# Sheet1.net
KiCad netlist of a schematic drawn in Altium Designer
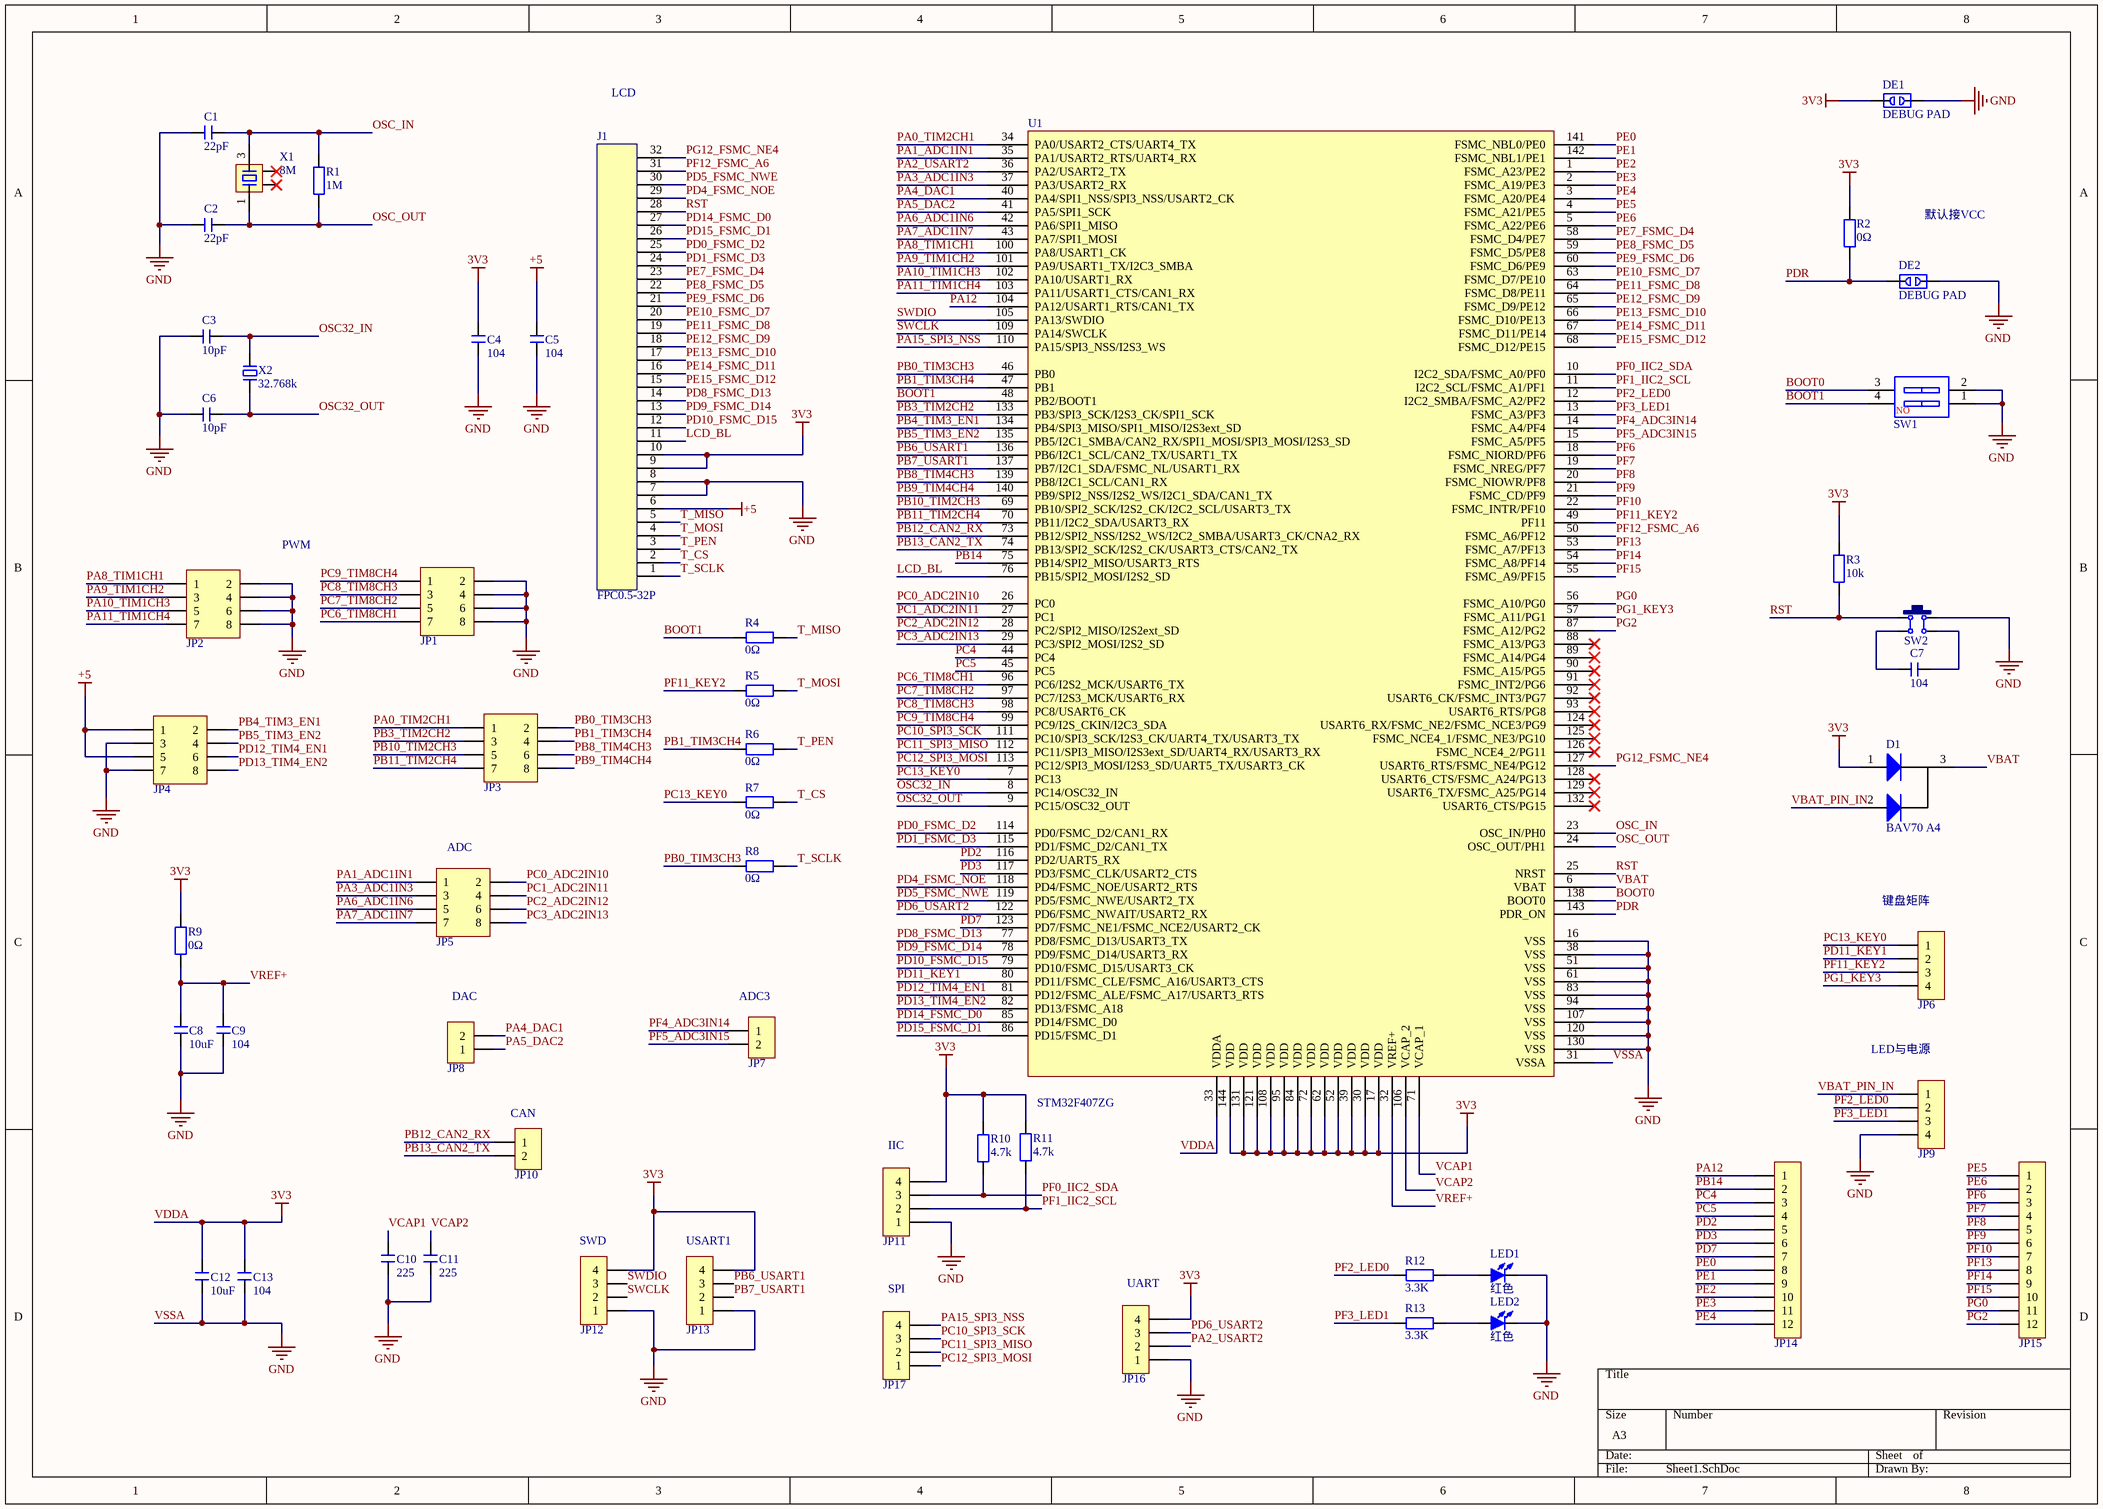
[diagram p0: Sheet1.SchDoc]

(export (version "E")
  (design (tool "Eeschema 10.0.6"))
  (components
    (comp (ref "C1")
      (value "22pF")
      (footprint "C 0603_L")
      (description "无极性贴片电容")
      (fields (field (name "版权归属") "源创客"))
      (libsource (lib "3.1   - 电阻-电容-电感") (part "C"))
    )
    (comp (ref "C2")
      (value "22pF")
      (footprint "C 0603_L")
      (description "无极性贴片电容")
      (fields (field (name "版权归属") "源创客"))
      (libsource (lib "3.1   - 电阻-电容-电感") (part "C"))
    )
    (comp (ref "C3")
      (value "10pF")
      (footprint "C 0603_L")
      (description "无极性贴片电容")
      (fields (field (name "版权归属") "源创客"))
      (libsource (lib "3.1   - 电阻-电容-电感") (part "C"))
    )
    (comp (ref "C4")
      (value "104")
      (footprint "C 0603_L")
      (description "无极性贴片电容")
      (fields (field (name "版权归属") "源创客"))
      (libsource (lib "3.1   - 电阻-电容-电感") (part "C"))
    )
    (comp (ref "C5")
      (value "104")
      (footprint "C 0603_L")
      (description "无极性贴片电容")
      (fields (field (name "版权归属") "源创客"))
      (libsource (lib "3.1   - 电阻-电容-电感") (part "C"))
    )
    (comp (ref "C6")
      (value "10pF")
      (footprint "C 0603_L")
      (description "无极性贴片电容")
      (fields (field (name "版权归属") "源创客"))
      (libsource (lib "3.1   - 电阻-电容-电感") (part "C"))
    )
    (comp (ref "C7")
      (value "104")
      (footprint "C 0603_L")
      (description "无极性贴片电容")
      (fields (field (name "版权归属") "源创客"))
      (libsource (lib "3.1   - 电阻-电容-电感") (part "C"))
    )
    (comp (ref "C8")
      (value "10uF")
      (footprint "C 0603_L")
      (description "无极性贴片电容")
      (fields (field (name "版权归属") "源创客"))
      (libsource (lib "3.1   - 电阻-电容-电感") (part "C"))
    )
    (comp (ref "C9")
      (value "104")
      (footprint "C 0603_L")
      (description "无极性贴片电容")
      (fields (field (name "版权归属") "源创客"))
      (libsource (lib "3.1   - 电阻-电容-电感") (part "C"))
    )
    (comp (ref "C10")
      (value "225")
      (footprint "C 0603_L")
      (description "无极性贴片电容")
      (fields (field (name "版权归属") "源创客"))
      (libsource (lib "3.1   - 电阻-电容-电感") (part "C"))
    )
    (comp (ref "C11")
      (value "225")
      (footprint "C 0603_L")
      (description "无极性贴片电容")
      (fields (field (name "版权归属") "源创客"))
      (libsource (lib "3.1   - 电阻-电容-电感") (part "C"))
    )
    (comp (ref "C12")
      (value "10uF")
      (footprint "C 0603_L")
      (description "无极性贴片电容")
      (fields (field (name "版权归属") "源创客"))
      (libsource (lib "3.1   - 电阻-电容-电感") (part "C"))
    )
    (comp (ref "C13")
      (value "104")
      (footprint "C 0603_L")
      (description "无极性贴片电容")
      (fields (field (name "版权归属") "源创客"))
      (libsource (lib "3.1   - 电阻-电容-电感") (part "C"))
    )
    (comp (ref "D1")
      (value "BAV70 A4")
      (footprint "SOT-23(SOT-23-3)")
      (description "开关二极管")
      (libsource (lib "Miscellaneous Devices LC") (part "SOT-23 BAV70 A4"))
    )
    (comp (ref "DE1")
      (value "DEBUG PAD")
      (footprint "DEBUG_A")
      (description "调试断点焊盘")
      (fields (field (name "版权归属") "源创客"))
      (libsource (lib "15.1 - 未分类器件") (part "DEBUG"))
    )
    (comp (ref "DE2")
      (value "DEBUG PAD")
      (footprint "DEBUG_A")
      (description "调试断点焊盘")
      (fields (field (name "版权归属") "源创客"))
      (libsource (lib "15.1 - 未分类器件") (part "DEBUG"))
    )
    (comp (ref "J1")
      (value "FPC0.5-32P")
      (footprint "FPC0.5-32P")
      (description "贴片")
      (libsource (lib "FPC") (part "FPC0.5-32P"))
    )
    (comp (ref "JP1")
      (value "Header 4X2")
      (footprint "HDR2.54-LI-2x4P")
      (description "4*2P接插件")
      (fields (field (name "版权归属") "源创客"))
      (libsource (lib "4.5   - 接插件-脚距2.54") (part "Header 4X2"))
    )
    (comp (ref "JP2")
      (value "Header 4X2")
      (footprint "HDR2.54-LI-2x4P")
      (description "4*2P接插件")
      (fields (field (name "版权归属") "源创客"))
      (libsource (lib "4.5   - 接插件-脚距2.54") (part "Header 4X2"))
    )
    (comp (ref "JP3")
      (value "Header 4X2")
      (footprint "HDR2.54-LI-2x4P")
      (description "4*2P接插件")
      (fields (field (name "版权归属") "源创客"))
      (libsource (lib "4.5   - 接插件-脚距2.54") (part "Header 4X2"))
    )
    (comp (ref "JP4")
      (value "Header 4X2")
      (footprint "HDR2.54-LI-2x4P")
      (description "4*2P接插件")
      (fields (field (name "版权归属") "源创客"))
      (libsource (lib "4.5   - 接插件-脚距2.54") (part "Header 4X2"))
    )
    (comp (ref "JP5")
      (value "Header 4X2")
      (footprint "HDR2.54-LI-2x4P")
      (description "4*2P接插件")
      (fields (field (name "版权归属") "源创客"))
      (libsource (lib "4.5   - 接插件-脚距2.54") (part "Header 4X2"))
    )
    (comp (ref "JP6")
      (value "HDR-1X4")
      (footprint "HDR2.54-LI-4P")
      (description "4P接插件")
      (fields (field (name "版权归属") "源创客"))
      (libsource (lib "") (part "Header 4_1"))
    )
    (comp (ref "JP7")
      (value "HDR-1X2")
      (footprint "KF128-3.81-2P")
      (description "2P接插件")
      (fields (field (name "版权归属") "源创客"))
      (libsource (lib "4.7   - 接插件-脚距3.81") (part "Header 2"))
    )
    (comp (ref "JP8")
      (value "HDR-1X2")
      (footprint "HDR2.54-LI-2P")
      (description "2P接插件")
      (fields (field (name "版权归属") "源创客"))
      (libsource (lib "4.5   - 接插件-脚距2.54") (part "Header 2"))
    )
    (comp (ref "JP9")
      (value "HDR-1X4")
      (footprint "HDR2.54-LI-4P")
      (description "4P接插件")
      (fields (field (name "版权归属") "源创客"))
      (libsource (lib "") (part "Header 4_1"))
    )
    (comp (ref "JP10")
      (value "HDR-1X2")
      (footprint "KF350-2P")
      (description "2P接插件")
      (fields (field (name "版权归属") "源创客"))
      (libsource (lib "4.6   - 接插件-脚距3.5") (part "Header 2"))
    )
    (comp (ref "JP11")
      (value "HDR-1X4")
      (footprint "HDR2.54-LI-4P")
      (description "4P接插件")
      (fields (field (name "版权归属") "源创客"))
      (libsource (lib "4.5   - 接插件-脚距2.54") (part "Header 4"))
    )
    (comp (ref "JP12")
      (value "HDR-1X4")
      (footprint "HDR2.54-LI-4P")
      (description "4P接插件")
      (fields (field (name "版权归属") "源创客"))
      (libsource (lib "4.5   - 接插件-脚距2.54") (part "Header 4"))
    )
    (comp (ref "JP13")
      (value "HDR-1X4")
      (footprint "HDR2.54-LI-4P")
      (description "4P接插件")
      (fields (field (name "版权归属") "源创客"))
      (libsource (lib "4.5   - 接插件-脚距2.54") (part "Header 4"))
    )
    (comp (ref "JP14")
      (value "HDR-1X12")
      (footprint "HDR2.54-LI-12P")
      (description "12P接插件")
      (fields (field (name "版权归属") "源创客"))
      (libsource (lib "4.5   - 接插件-脚距2.54") (part "Header 12"))
    )
    (comp (ref "JP15")
      (value "HDR-1X12")
      (footprint "HDR2.54-LI-12P")
      (description "12P接插件")
      (fields (field (name "版权归属") "源创客"))
      (libsource (lib "4.5   - 接插件-脚距2.54") (part "Header 12"))
    )
    (comp (ref "JP16")
      (value "HDR-1X4")
      (footprint "HDR2.54-LI-4P")
      (description "4P接插件")
      (fields (field (name "版权归属") "源创客"))
      (libsource (lib "4.5   - 接插件-脚距2.54") (part "Header 4"))
    )
    (comp (ref "JP17")
      (value "HDR-1X4")
      (footprint "HDR2.54-LI-4P")
      (description "4P接插件")
      (fields (field (name "版权归属") "源创客"))
      (libsource (lib "4.5   - 接插件-脚距2.54") (part "Header 4"))
    )
    (comp (ref "LED1")
      (value "红色")
      (footprint "LED 0603R")
      (description "贴片LED")
      (fields (field (name "版权归属") "源创客"))
      (libsource (lib "9.1   - LED") (part "LED-SMD"))
    )
    (comp (ref "LED2")
      (value "红色")
      (footprint "LED 0603B")
      (description "贴片LED")
      (fields (field (name "版权归属") "源创客"))
      (libsource (lib "9.1   - LED") (part "LED-SMD"))
    )
    (comp (ref "R1")
      (value "1M")
      (footprint "R 0603_L")
      (description "贴片电阻")
      (fields (field (name "版权归属") "源创客"))
      (libsource (lib "3.1   - 电阻-电容-电感") (part "R"))
    )
    (comp (ref "R2")
      (value "0Ω")
      (footprint "R 0603_L")
      (description "贴片电阻")
      (fields (field (name "版权归属") "源创客"))
      (libsource (lib "3.1   - 电阻-电容-电感") (part "R"))
    )
    (comp (ref "R3")
      (value "10k")
      (footprint "R 0603_L")
      (description "贴片电阻")
      (fields (field (name "版权归属") "源创客"))
      (libsource (lib "3.1   - 电阻-电容-电感") (part "R"))
    )
    (comp (ref "R4")
      (value "0Ω")
      (footprint "R 0603_L")
      (description "贴片电阻")
      (fields (field (name "版权归属") "源创客"))
      (libsource (lib "3.1   - 电阻-电容-电感") (part "R"))
    )
    (comp (ref "R5")
      (value "0Ω")
      (footprint "R 0603_L")
      (description "贴片电阻")
      (fields (field (name "版权归属") "源创客"))
      (libsource (lib "3.1   - 电阻-电容-电感") (part "R"))
    )
    (comp (ref "R6")
      (value "0Ω")
      (footprint "R 0603_L")
      (description "贴片电阻")
      (fields (field (name "版权归属") "源创客"))
      (libsource (lib "3.1   - 电阻-电容-电感") (part "R"))
    )
    (comp (ref "R7")
      (value "0Ω")
      (footprint "R 0603_L")
      (description "贴片电阻")
      (fields (field (name "版权归属") "源创客"))
      (libsource (lib "3.1   - 电阻-电容-电感") (part "R"))
    )
    (comp (ref "R8")
      (value "0Ω")
      (footprint "R 0603_L")
      (description "贴片电阻")
      (fields (field (name "版权归属") "源创客"))
      (libsource (lib "3.1   - 电阻-电容-电感") (part "R"))
    )
    (comp (ref "R9")
      (value "0Ω")
      (footprint "R 0603_L")
      (description "贴片电阻")
      (fields (field (name "版权归属") "源创客"))
      (libsource (lib "3.1   - 电阻-电容-电感") (part "R"))
    )
    (comp (ref "R10")
      (value "4.7k")
      (footprint "R 0603_L")
      (description "贴片电阻")
      (fields (field (name "版权归属") "源创客"))
      (libsource (lib "3.1   - 电阻-电容-电感") (part "R"))
    )
    (comp (ref "R11")
      (value "4.7k")
      (footprint "R 0603_L")
      (description "贴片电阻")
      (fields (field (name "版权归属") "源创客"))
      (libsource (lib "3.1   - 电阻-电容-电感") (part "R"))
    )
    (comp (ref "R12")
      (value "3.3K")
      (footprint "R 0603_L")
      (description "贴片电阻")
      (fields (field (name "版权归属") "源创客"))
      (libsource (lib "3.1   - 电阻-电容-电感") (part "R"))
    )
    (comp (ref "R13")
      (value "3.3K")
      (footprint "R 0603_L")
      (description "贴片电阻")
      (fields (field (name "版权归属") "源创客"))
      (libsource (lib "3.1   - 电阻-电容-电感") (part "R"))
    )
    (comp (ref "SW1")
      (value "CSW-2P")
      (footprint "CSW DIP-2P")
      (description "2路编码开关")
      (fields (field (name "版权归属") "源创客"))
      (libsource (lib "5.1   - 按键-开关") (part "CSW-2P"))
    )
    (comp (ref "SW2")
      (value "6x6x5")
      (footprint "TSW SMD-6*6*4.3")
      (description "贴片6x6轻触开关")
      (fields (field (name "版权归属") "源创客"))
      (libsource (lib "5.1   - 按键-开关") (part "TSW SMD-6x6"))
    )
    (comp (ref "U1")
      (value "STM32F407ZG")
      (footprint "LQFP144 20X20_L")
      (description "Flaah:1024/RAM:192/IO:114")
      (fields (field (name "版权归属") "源创客"))
      (libsource (lib "2.1   - STM32系列单片机") (part "STM32F407ZG"))
    )
    (comp (ref "X1")
      (value "8M")
      (footprint "OSC 1612-4P")
      (description "4脚无源晶振")
      (fields (field (name "版权归属") "源创客"))
      (libsource (lib "10.1 - 保险丝-晶振") (part "XTAL-4P"))
    )
    (comp (ref "X2")
      (value "32.768k")
      (footprint "OSC HC-49S")
      (description "2脚无源脚晶振")
      (fields (field (name "版权归属") "源创客"))
      (libsource (lib "10.1 - 保险丝-晶振") (part "XTAL-2P"))
    )
  )
  (nets
    (net (code "1") (name "+5") (class "Default")
      (node (ref "C5") (pin "2") (pinfunction "2_2") (pintype "passive"))
      (node (ref "J1") (pin "6") (pinfunction "6_6") (pintype "passive"))
      (node (ref "JP4") (pin "1") (pinfunction "1_1") (pintype "passive"))
      (node (ref "JP4") (pin "5") (pinfunction "5_5") (pintype "passive"))
    )
    (net (code "2") (name "/BOOT0") (class "Default")
      (node (ref "SW1") (pin "3") (pinfunction "3_3") (pintype "passive"))
      (node (ref "U1") (pin "138") (pinfunction "BOOT0_138") (pintype "passive"))
    )
    (net (code "3") (name "/BOOT1") (class "Default")
      (node (ref "R4") (pin "2") (pinfunction "2_2") (pintype "passive"))
      (node (ref "SW1") (pin "4") (pinfunction "4_4") (pintype "passive"))
      (node (ref "U1") (pin "48") (pinfunction "PB2/BOOT1_48") (pintype "passive"))
    )
    (net (code "4") (name "/LCD_BL") (class "Default")
      (node (ref "J1") (pin "11") (pinfunction "11_11") (pintype "passive"))
      (node (ref "U1") (pin "76") (pinfunction "PB15/SPI2_MOSI/I2S2_SD_76") (pintype "passive"))
    )
    (net (code "5") (name "/OSC32_IN") (class "Default")
      (node (ref "C3") (pin "1") (pinfunction "1_1") (pintype "passive"))
      (node (ref "U1") (pin "8") (pinfunction "PC14/OSC32_IN_8") (pintype "passive"))
      (node (ref "X2") (pin "2") (pinfunction "2_2") (pintype "passive"))
    )
    (net (code "6") (name "/OSC32_OUT") (class "Default")
      (node (ref "C6") (pin "1") (pinfunction "1_1") (pintype "passive"))
      (node (ref "U1") (pin "9") (pinfunction "PC15/OSC32_OUT_9") (pintype "passive"))
      (node (ref "X2") (pin "1") (pinfunction "1_1") (pintype "passive"))
    )
    (net (code "7") (name "/OSC_IN") (class "Default")
      (node (ref "C1") (pin "1") (pinfunction "1_1") (pintype "passive"))
      (node (ref "R1") (pin "1") (pinfunction "1_1") (pintype "passive"))
      (node (ref "U1") (pin "23") (pinfunction "OSC_IN/PH0_23") (pintype "passive"))
      (node (ref "X1") (pin "3") (pinfunction "3_3") (pintype "passive"))
    )
    (net (code "8") (name "/OSC_OUT") (class "Default")
      (node (ref "C2") (pin "1") (pinfunction "1_1") (pintype "passive"))
      (node (ref "R1") (pin "2") (pinfunction "2_2") (pintype "passive"))
      (node (ref "U1") (pin "24") (pinfunction "OSC_OUT/PH1_24") (pintype "passive"))
      (node (ref "X1") (pin "1") (pinfunction "1_1") (pintype "passive"))
    )
    (net (code "9") (name "/PA0_TIM2CH1") (class "Default")
      (node (ref "JP3") (pin "1") (pinfunction "1_1") (pintype "passive"))
      (node (ref "U1") (pin "34") (pinfunction "PA0/USART2_CTS/UART4_TX_34") (pintype "passive"))
    )
    (net (code "10") (name "/PA1_ADC1IN1") (class "Default")
      (node (ref "JP5") (pin "1") (pinfunction "1_1") (pintype "passive"))
      (node (ref "U1") (pin "35") (pinfunction "PA1/USART2_RTS/UART4_RX_35") (pintype "passive"))
    )
    (net (code "11") (name "/PA2_USART2") (class "Default")
      (node (ref "JP16") (pin "2") (pinfunction "2_2") (pintype "passive"))
      (node (ref "U1") (pin "36") (pinfunction "PA2/USART2_TX_36") (pintype "passive"))
    )
    (net (code "12") (name "/PA3_ADC1IN3") (class "Default")
      (node (ref "JP5") (pin "3") (pinfunction "3_3") (pintype "passive"))
      (node (ref "U1") (pin "37") (pinfunction "PA3/USART2_RX_37") (pintype "passive"))
    )
    (net (code "13") (name "/PA4_DAC1") (class "Default")
      (node (ref "JP8") (pin "2") (pinfunction "2_2") (pintype "passive"))
      (node (ref "U1") (pin "40") (pinfunction "PA4/SPI1_NSS/SPI3_NSS/USART2_CK_40") (pintype "passive"))
    )
    (net (code "14") (name "/PA5_DAC2") (class "Default")
      (node (ref "JP8") (pin "1") (pinfunction "1_1") (pintype "passive"))
      (node (ref "U1") (pin "41") (pinfunction "PA5/SPI1_SCK_41") (pintype "passive"))
    )
    (net (code "15") (name "/PA6_ADC1IN6") (class "Default")
      (node (ref "JP5") (pin "5") (pinfunction "5_5") (pintype "passive"))
      (node (ref "U1") (pin "42") (pinfunction "PA6/SPI1_MISO_42") (pintype "passive"))
    )
    (net (code "16") (name "/PA7_ADC1IN7") (class "Default")
      (node (ref "JP5") (pin "7") (pinfunction "7_7") (pintype "passive"))
      (node (ref "U1") (pin "43") (pinfunction "PA7/SPI1_MOSI_43") (pintype "passive"))
    )
    (net (code "17") (name "/PA8_TIM1CH1") (class "Default")
      (node (ref "JP2") (pin "1") (pinfunction "1_1") (pintype "passive"))
      (node (ref "U1") (pin "100") (pinfunction "PA8/USART1_CK_100") (pintype "passive"))
    )
    (net (code "18") (name "/PA9_TIM1CH2") (class "Default")
      (node (ref "JP2") (pin "3") (pinfunction "3_3") (pintype "passive"))
      (node (ref "U1") (pin "101") (pinfunction "PA9/USART1_TX/I2C3_SMBA_101") (pintype "passive"))
    )
    (net (code "19") (name "/PA10_TIM1CH3") (class "Default")
      (node (ref "JP2") (pin "5") (pinfunction "5_5") (pintype "passive"))
      (node (ref "U1") (pin "102") (pinfunction "PA10/USART1_RX_102") (pintype "passive"))
    )
    (net (code "20") (name "/PA11_TIM1CH4") (class "Default")
      (node (ref "JP2") (pin "7") (pinfunction "7_7") (pintype "passive"))
      (node (ref "U1") (pin "103") (pinfunction "PA11/USART1_CTS/CAN1_RX_103") (pintype "passive"))
    )
    (net (code "21") (name "/PA12") (class "Default")
      (node (ref "JP14") (pin "1") (pinfunction "1_1") (pintype "passive"))
      (node (ref "U1") (pin "104") (pinfunction "PA12/USART1_RTS/CAN1_TX_104") (pintype "passive"))
    )
    (net (code "22") (name "/PA15_SPI3_NSS") (class "Default")
      (node (ref "JP17") (pin "4") (pinfunction "4_4") (pintype "passive"))
      (node (ref "U1") (pin "110") (pinfunction "PA15/SPI3_NSS/I2S3_WS_110") (pintype "passive"))
    )
    (net (code "23") (name "/PB0_TIM3CH3") (class "Default")
      (node (ref "JP3") (pin "2") (pinfunction "2_2") (pintype "passive"))
      (node (ref "R8") (pin "2") (pinfunction "2_2") (pintype "passive"))
      (node (ref "U1") (pin "46") (pinfunction "PB0_46") (pintype "passive"))
    )
    (net (code "24") (name "/PB1_TIM3CH4") (class "Default")
      (node (ref "JP3") (pin "4") (pinfunction "4_4") (pintype "passive"))
      (node (ref "R6") (pin "2") (pinfunction "2_2") (pintype "passive"))
      (node (ref "U1") (pin "47") (pinfunction "PB1_47") (pintype "passive"))
    )
    (net (code "25") (name "/PB3_TIM2CH2") (class "Default")
      (node (ref "JP3") (pin "3") (pinfunction "3_3") (pintype "passive"))
      (node (ref "U1") (pin "133") (pinfunction "PB3/SPI3_SCK/I2S3_CK/SPI1_SCK_133") (pintype "passive"))
    )
    (net (code "26") (name "/PB4_TIM3_EN1") (class "Default")
      (node (ref "JP4") (pin "2") (pinfunction "2_2") (pintype "passive"))
      (node (ref "U1") (pin "134") (pinfunction "PB4/SPI3_MISO/SPI1_MISO/I2S3ext_SD_134") (pintype "passive"))
    )
    (net (code "27") (name "/PB5_TIM3_EN2") (class "Default")
      (node (ref "JP4") (pin "4") (pinfunction "4_4") (pintype "passive"))
      (node (ref "U1") (pin "135") (pinfunction "PB5/I2C1_SMBA/CAN2_RX/SPI1_MOSI/SPI3_MOSI/I2S3_SD_135") (pintype "passive"))
    )
    (net (code "28") (name "/PB6_USART1") (class "Default")
      (node (ref "JP13") (pin "3") (pinfunction "3_3") (pintype "passive"))
      (node (ref "U1") (pin "136") (pinfunction "PB6/I2C1_SCL/CAN2_TX/USART1_TX_136") (pintype "passive"))
    )
    (net (code "29") (name "/PB7_USART1") (class "Default")
      (node (ref "JP13") (pin "2") (pinfunction "2_2") (pintype "passive"))
      (node (ref "U1") (pin "137") (pinfunction "PB7/I2C1_SDA/FSMC_NL/USART1_RX_137") (pintype "passive"))
    )
    (net (code "30") (name "/PB8_TIM4CH3") (class "Default")
      (node (ref "JP3") (pin "6") (pinfunction "6_6") (pintype "passive"))
      (node (ref "U1") (pin "139") (pinfunction "PB8/I2C1_SCL/CAN1_RX_139") (pintype "passive"))
    )
    (net (code "31") (name "/PB9_TIM4CH4") (class "Default")
      (node (ref "JP3") (pin "8") (pinfunction "8_8") (pintype "passive"))
      (node (ref "U1") (pin "140") (pinfunction "PB9/SPI2_NSS/I2S2_WS/I2C1_SDA/CAN1_TX_140") (pintype "passive"))
    )
    (net (code "32") (name "/PB10_TIM2CH3") (class "Default")
      (node (ref "JP3") (pin "5") (pinfunction "5_5") (pintype "passive"))
      (node (ref "U1") (pin "69") (pinfunction "PB10/SPI2_SCK/I2S2_CK/I2C2_SCL/USART3_TX_69") (pintype "passive"))
    )
    (net (code "33") (name "/PB11_TIM2CH4") (class "Default")
      (node (ref "JP3") (pin "7") (pinfunction "7_7") (pintype "passive"))
      (node (ref "U1") (pin "70") (pinfunction "PB11/I2C2_SDA/USART3_RX_70") (pintype "passive"))
    )
    (net (code "34") (name "/PB12_CAN2_RX") (class "Default")
      (node (ref "JP10") (pin "1") (pinfunction "1_1") (pintype "passive"))
      (node (ref "U1") (pin "73") (pinfunction "PB12/SPI2_NSS/I2S2_WS/I2C2_SMBA/USART3_CK/CNA2_RX_73") (pintype "passive"))
    )
    (net (code "35") (name "/PB13_CAN2_TX") (class "Default")
      (node (ref "JP10") (pin "2") (pinfunction "2_2") (pintype "passive"))
      (node (ref "U1") (pin "74") (pinfunction "PB13/SPI2_SCK/I2S2_CK/USART3_CTS/CAN2_TX_74") (pintype "passive"))
    )
    (net (code "36") (name "/PB14") (class "Default")
      (node (ref "JP14") (pin "2") (pinfunction "2_2") (pintype "passive"))
      (node (ref "U1") (pin "75") (pinfunction "PB14/SPI2_MISO/USART3_RTS_75") (pintype "passive"))
    )
    (net (code "37") (name "/PC0_ADC2IN10") (class "Default")
      (node (ref "JP5") (pin "2") (pinfunction "2_2") (pintype "passive"))
      (node (ref "U1") (pin "26") (pinfunction "PC0_26") (pintype "passive"))
    )
    (net (code "38") (name "/PC1_ADC2IN11") (class "Default")
      (node (ref "JP5") (pin "4") (pinfunction "4_4") (pintype "passive"))
      (node (ref "U1") (pin "27") (pinfunction "PC1_27") (pintype "passive"))
    )
    (net (code "39") (name "/PC2_ADC2IN12") (class "Default")
      (node (ref "JP5") (pin "6") (pinfunction "6_6") (pintype "passive"))
      (node (ref "U1") (pin "28") (pinfunction "PC2/SPI2_MISO/I2S2ext_SD_28") (pintype "passive"))
    )
    (net (code "40") (name "/PC3_ADC2IN13") (class "Default")
      (node (ref "JP5") (pin "8") (pinfunction "8_8") (pintype "passive"))
      (node (ref "U1") (pin "29") (pinfunction "PC3/SPI2_MOSI/I2S2_SD_29") (pintype "passive"))
    )
    (net (code "41") (name "/PC4") (class "Default")
      (node (ref "JP14") (pin "3") (pinfunction "3_3") (pintype "passive"))
      (node (ref "U1") (pin "44") (pinfunction "PC4_44") (pintype "passive"))
    )
    (net (code "42") (name "/PC5") (class "Default")
      (node (ref "JP14") (pin "4") (pinfunction "4_4") (pintype "passive"))
      (node (ref "U1") (pin "45") (pinfunction "PC5_45") (pintype "passive"))
    )
    (net (code "43") (name "/PC6_TIM8CH1") (class "Default")
      (node (ref "JP1") (pin "7") (pinfunction "7_7") (pintype "passive"))
      (node (ref "U1") (pin "96") (pinfunction "PC6/I2S2_MCK/USART6_TX_96") (pintype "passive"))
    )
    (net (code "44") (name "/PC7_TIM8CH2") (class "Default")
      (node (ref "JP1") (pin "5") (pinfunction "5_5") (pintype "passive"))
      (node (ref "U1") (pin "97") (pinfunction "PC7/I2S3_MCK/USART6_RX_97") (pintype "passive"))
    )
    (net (code "45") (name "/PC8_TIM8CH3") (class "Default")
      (node (ref "JP1") (pin "3") (pinfunction "3_3") (pintype "passive"))
      (node (ref "U1") (pin "98") (pinfunction "PC8/USART6_CK_98") (pintype "passive"))
    )
    (net (code "46") (name "/PC9_TIM8CH4") (class "Default")
      (node (ref "JP1") (pin "1") (pinfunction "1_1") (pintype "passive"))
      (node (ref "U1") (pin "99") (pinfunction "PC9/I2S_CKIN/I2C3_SDA_99") (pintype "passive"))
    )
    (net (code "47") (name "/PC10_SPI3_SCK") (class "Default")
      (node (ref "JP17") (pin "3") (pinfunction "3_3") (pintype "passive"))
      (node (ref "U1") (pin "111") (pinfunction "PC10/SPI3_SCK/I2S3_CK/UART4_TX/USART3_TX_111") (pintype "passive"))
    )
    (net (code "48") (name "/PC11_SPI3_MISO") (class "Default")
      (node (ref "JP17") (pin "2") (pinfunction "2_2") (pintype "passive"))
      (node (ref "U1") (pin "112") (pinfunction "PC11/SPI3_MISO/I2S3ext_SD/UART4_RX/USART3_RX_112") (pintype "passive"))
    )
    (net (code "49") (name "/PC12_SPI3_MOSI") (class "Default")
      (node (ref "JP17") (pin "1") (pinfunction "1_1") (pintype "passive"))
      (node (ref "U1") (pin "113") (pinfunction "PC12/SPI3_MOSI/I2S3_SD/UART5_TX/USART3_CK_113") (pintype "passive"))
    )
    (net (code "50") (name "/PC13_KEY0") (class "Default")
      (node (ref "JP6") (pin "1") (pinfunction "1_1") (pintype "passive"))
      (node (ref "R7") (pin "2") (pinfunction "2_2") (pintype "passive"))
      (node (ref "U1") (pin "7") (pinfunction "PC13_7") (pintype "passive"))
    )
    (net (code "51") (name "/PD0_FSMC_D2") (class "Default")
      (node (ref "J1") (pin "25") (pinfunction "25_25") (pintype "passive"))
      (node (ref "U1") (pin "114") (pinfunction "PD0/FSMC_D2/CAN1_RX_114") (pintype "passive"))
    )
    (net (code "52") (name "/PD1_FSMC_D3") (class "Default")
      (node (ref "J1") (pin "24") (pinfunction "24_24") (pintype "passive"))
      (node (ref "U1") (pin "115") (pinfunction "PD1/FSMC_D2/CAN1_TX_115") (pintype "passive"))
    )
    (net (code "53") (name "/PD2") (class "Default")
      (node (ref "JP14") (pin "5") (pinfunction "5_5") (pintype "passive"))
      (node (ref "U1") (pin "116") (pinfunction "PD2/UART5_RX_116") (pintype "passive"))
    )
    (net (code "54") (name "/PD3") (class "Default")
      (node (ref "JP14") (pin "6") (pinfunction "6_6") (pintype "passive"))
      (node (ref "U1") (pin "117") (pinfunction "PD3/FSMC_CLK/USART2_CTS_117") (pintype "passive"))
    )
    (net (code "55") (name "/PD4_FSMC_NOE") (class "Default")
      (node (ref "J1") (pin "29") (pinfunction "29_29") (pintype "passive"))
      (node (ref "U1") (pin "118") (pinfunction "PD4/FSMC_NOE/USART2_RTS_118") (pintype "passive"))
    )
    (net (code "56") (name "/PD5_FSMC_NWE") (class "Default")
      (node (ref "J1") (pin "30") (pinfunction "30_30") (pintype "passive"))
      (node (ref "U1") (pin "119") (pinfunction "PD5/FSMC_NWE/USART2_TX_119") (pintype "passive"))
    )
    (net (code "57") (name "/PD6_USART2") (class "Default")
      (node (ref "JP16") (pin "3") (pinfunction "3_3") (pintype "passive"))
      (node (ref "U1") (pin "122") (pinfunction "PD6/FSMC_NWAIT/USART2_RX_122") (pintype "passive"))
    )
    (net (code "58") (name "/PD7") (class "Default")
      (node (ref "JP14") (pin "7") (pinfunction "7_7") (pintype "passive"))
      (node (ref "U1") (pin "123") (pinfunction "PD7/FSMC_NE1/FSMC_NCE2/USART2_CK_123") (pintype "passive"))
    )
    (net (code "59") (name "/PD8_FSMC_D13") (class "Default")
      (node (ref "J1") (pin "14") (pinfunction "14_14") (pintype "passive"))
      (node (ref "U1") (pin "77") (pinfunction "PD8/FSMC_D13/USART3_TX_77") (pintype "passive"))
    )
    (net (code "60") (name "/PD9_FSMC_D14") (class "Default")
      (node (ref "J1") (pin "13") (pinfunction "13_13") (pintype "passive"))
      (node (ref "U1") (pin "78") (pinfunction "PD9/FSMC_D14/USART3_RX_78") (pintype "passive"))
    )
    (net (code "61") (name "/PD10_FSMC_D15") (class "Default")
      (node (ref "J1") (pin "12") (pinfunction "12_12") (pintype "passive"))
      (node (ref "U1") (pin "79") (pinfunction "PD10/FSMC_D15/USART3_CK_79") (pintype "passive"))
    )
    (net (code "62") (name "/PD11_KEY1") (class "Default")
      (node (ref "JP6") (pin "2") (pinfunction "2_2") (pintype "passive"))
      (node (ref "U1") (pin "80") (pinfunction "PD11/FSMC_CLE/FSMC_A16/USART3_CTS_80") (pintype "passive"))
    )
    (net (code "63") (name "/PD12_TIM4_EN1") (class "Default")
      (node (ref "JP4") (pin "6") (pinfunction "6_6") (pintype "passive"))
      (node (ref "U1") (pin "81") (pinfunction "PD12/FSMC_ALE/FSMC_A17/USART3_RTS_81") (pintype "passive"))
    )
    (net (code "64") (name "/PD13_TIM4_EN2") (class "Default")
      (node (ref "JP4") (pin "8") (pinfunction "8_8") (pintype "passive"))
      (node (ref "U1") (pin "82") (pinfunction "PD13/FSMC_A18_82") (pintype "passive"))
    )
    (net (code "65") (name "/PD14_FSMC_D0") (class "Default")
      (node (ref "J1") (pin "27") (pinfunction "27_27") (pintype "passive"))
      (node (ref "U1") (pin "85") (pinfunction "PD14/FSMC_D0_85") (pintype "passive"))
    )
    (net (code "66") (name "/PD15_FSMC_D1") (class "Default")
      (node (ref "J1") (pin "26") (pinfunction "26_26") (pintype "passive"))
      (node (ref "U1") (pin "86") (pinfunction "PD15/FSMC_D1_86") (pintype "passive"))
    )
    (net (code "67") (name "/PDR") (class "Default")
      (node (ref "DE2") (pin "1") (pinfunction "1_1") (pintype "passive"))
      (node (ref "R2") (pin "1") (pinfunction "1_1") (pintype "passive"))
      (node (ref "U1") (pin "143") (pinfunction "PDR_ON_143") (pintype "passive"))
    )
    (net (code "68") (name "/PE0") (class "Default")
      (node (ref "JP14") (pin "8") (pinfunction "8_8") (pintype "passive"))
      (node (ref "U1") (pin "141") (pinfunction "FSMC_NBL0/PE0_141") (pintype "passive"))
    )
    (net (code "69") (name "/PE1") (class "Default")
      (node (ref "JP14") (pin "9") (pinfunction "9_9") (pintype "passive"))
      (node (ref "U1") (pin "142") (pinfunction "FSMC_NBL1/PE1_142") (pintype "passive"))
    )
    (net (code "70") (name "/PE2") (class "Default")
      (node (ref "JP14") (pin "10") (pinfunction "10_10") (pintype "passive"))
      (node (ref "U1") (pin "1") (pinfunction "FSMC_A23/PE2_1") (pintype "passive"))
    )
    (net (code "71") (name "/PE3") (class "Default")
      (node (ref "JP14") (pin "11") (pinfunction "11_11") (pintype "passive"))
      (node (ref "U1") (pin "2") (pinfunction "FSMC_A19/PE3_2") (pintype "passive"))
    )
    (net (code "72") (name "/PE4") (class "Default")
      (node (ref "JP14") (pin "12") (pinfunction "12_12") (pintype "passive"))
      (node (ref "U1") (pin "3") (pinfunction "FSMC_A20/PE4_3") (pintype "passive"))
    )
    (net (code "73") (name "/PE5") (class "Default")
      (node (ref "JP15") (pin "1") (pinfunction "1_1") (pintype "passive"))
      (node (ref "U1") (pin "4") (pinfunction "FSMC_A21/PE5_4") (pintype "passive"))
    )
    (net (code "74") (name "/PE6") (class "Default")
      (node (ref "JP15") (pin "2") (pinfunction "2_2") (pintype "passive"))
      (node (ref "U1") (pin "5") (pinfunction "FSMC_A22/PE6_5") (pintype "passive"))
    )
    (net (code "75") (name "/PE7_FSMC_D4") (class "Default")
      (node (ref "J1") (pin "23") (pinfunction "23_23") (pintype "passive"))
      (node (ref "U1") (pin "58") (pinfunction "FSMC_D4/PE7_58") (pintype "passive"))
    )
    (net (code "76") (name "/PE8_FSMC_D5") (class "Default")
      (node (ref "J1") (pin "22") (pinfunction "22_22") (pintype "passive"))
      (node (ref "U1") (pin "59") (pinfunction "FSMC_D5/PE8_59") (pintype "passive"))
    )
    (net (code "77") (name "/PE9_FSMC_D6") (class "Default")
      (node (ref "J1") (pin "21") (pinfunction "21_21") (pintype "passive"))
      (node (ref "U1") (pin "60") (pinfunction "FSMC_D6/PE9_60") (pintype "passive"))
    )
    (net (code "78") (name "/PE10_FSMC_D7") (class "Default")
      (node (ref "J1") (pin "20") (pinfunction "20_20") (pintype "passive"))
      (node (ref "U1") (pin "63") (pinfunction "FSMC_D7/PE10_63") (pintype "passive"))
    )
    (net (code "79") (name "/PE11_FSMC_D8") (class "Default")
      (node (ref "J1") (pin "19") (pinfunction "19_19") (pintype "passive"))
      (node (ref "U1") (pin "64") (pinfunction "FSMC_D8/PE11_64") (pintype "passive"))
    )
    (net (code "80") (name "/PE12_FSMC_D9") (class "Default")
      (node (ref "J1") (pin "18") (pinfunction "18_18") (pintype "passive"))
      (node (ref "U1") (pin "65") (pinfunction "FSMC_D9/PE12_65") (pintype "passive"))
    )
    (net (code "81") (name "/PE13_FSMC_D10") (class "Default")
      (node (ref "J1") (pin "17") (pinfunction "17_17") (pintype "passive"))
      (node (ref "U1") (pin "66") (pinfunction "FSMC_D10/PE13_66") (pintype "passive"))
    )
    (net (code "82") (name "/PE14_FSMC_D11") (class "Default")
      (node (ref "J1") (pin "16") (pinfunction "16_16") (pintype "passive"))
      (node (ref "U1") (pin "67") (pinfunction "FSMC_D11/PE14_67") (pintype "passive"))
    )
    (net (code "83") (name "/PE15_FSMC_D12") (class "Default")
      (node (ref "J1") (pin "15") (pinfunction "15_15") (pintype "passive"))
      (node (ref "U1") (pin "68") (pinfunction "FSMC_D12/PE15_68") (pintype "passive"))
    )
    (net (code "84") (name "/PF0_IIC2_SDA") (class "Default")
      (node (ref "JP11") (pin "3") (pinfunction "3_3") (pintype "passive"))
      (node (ref "R10") (pin "2") (pinfunction "2_2") (pintype "passive"))
      (node (ref "U1") (pin "10") (pinfunction "I2C2_SDA/FSMC_A0/PF0_10") (pintype "passive"))
    )
    (net (code "85") (name "/PF1_IIC2_SCL") (class "Default")
      (node (ref "JP11") (pin "2") (pinfunction "2_2") (pintype "passive"))
      (node (ref "R11") (pin "2") (pinfunction "2_2") (pintype "passive"))
      (node (ref "U1") (pin "11") (pinfunction "I2C2_SCL/FSMC_A1/PF1_11") (pintype "passive"))
    )
    (net (code "86") (name "/PF2_LED0") (class "Default")
      (node (ref "JP9") (pin "2") (pinfunction "2_2") (pintype "passive"))
      (node (ref "R12") (pin "1") (pinfunction "1_1") (pintype "passive"))
      (node (ref "U1") (pin "12") (pinfunction "I2C2_SMBA/FSMC_A2/PF2_12") (pintype "passive"))
    )
    (net (code "87") (name "/PF3_LED1") (class "Default")
      (node (ref "JP9") (pin "3") (pinfunction "3_3") (pintype "passive"))
      (node (ref "R13") (pin "1") (pinfunction "1_1") (pintype "passive"))
      (node (ref "U1") (pin "13") (pinfunction "FSMC_A3/PF3_13") (pintype "passive"))
    )
    (net (code "88") (name "/PF4_ADC3IN14") (class "Default")
      (node (ref "JP7") (pin "1") (pinfunction "1_1") (pintype "passive"))
      (node (ref "U1") (pin "14") (pinfunction "FSMC_A4/PF4_14") (pintype "passive"))
    )
    (net (code "89") (name "/PF5_ADC3IN15") (class "Default")
      (node (ref "JP7") (pin "2") (pinfunction "2_2") (pintype "passive"))
      (node (ref "U1") (pin "15") (pinfunction "FSMC_A5/PF5_15") (pintype "passive"))
    )
    (net (code "90") (name "/PF6") (class "Default")
      (node (ref "JP15") (pin "3") (pinfunction "3_3") (pintype "passive"))
      (node (ref "U1") (pin "18") (pinfunction "FSMC_NIORD/PF6_18") (pintype "passive"))
    )
    (net (code "91") (name "/PF7") (class "Default")
      (node (ref "JP15") (pin "4") (pinfunction "4_4") (pintype "passive"))
      (node (ref "U1") (pin "19") (pinfunction "FSMC_NREG/PF7_19") (pintype "passive"))
    )
    (net (code "92") (name "/PF8") (class "Default")
      (node (ref "JP15") (pin "5") (pinfunction "5_5") (pintype "passive"))
      (node (ref "U1") (pin "20") (pinfunction "FSMC_NIOWR/PF8_20") (pintype "passive"))
    )
    (net (code "93") (name "/PF9") (class "Default")
      (node (ref "JP15") (pin "6") (pinfunction "6_6") (pintype "passive"))
      (node (ref "U1") (pin "21") (pinfunction "FSMC_CD/PF9_21") (pintype "passive"))
    )
    (net (code "94") (name "/PF10") (class "Default")
      (node (ref "JP15") (pin "7") (pinfunction "7_7") (pintype "passive"))
      (node (ref "U1") (pin "22") (pinfunction "FSMC_INTR/PF10_22") (pintype "passive"))
    )
    (net (code "95") (name "/PF11_KEY2") (class "Default")
      (node (ref "JP6") (pin "3") (pinfunction "3_3") (pintype "passive"))
      (node (ref "R5") (pin "2") (pinfunction "2_2") (pintype "passive"))
      (node (ref "U1") (pin "49") (pinfunction "PF11_49") (pintype "passive"))
    )
    (net (code "96") (name "/PF12_FSMC_A6") (class "Default")
      (node (ref "J1") (pin "31") (pinfunction "31_31") (pintype "passive"))
      (node (ref "U1") (pin "50") (pinfunction "FSMC_A6/PF12_50") (pintype "passive"))
    )
    (net (code "97") (name "/PF13") (class "Default")
      (node (ref "JP15") (pin "8") (pinfunction "8_8") (pintype "passive"))
      (node (ref "U1") (pin "53") (pinfunction "FSMC_A7/PF13_53") (pintype "passive"))
    )
    (net (code "98") (name "/PF14") (class "Default")
      (node (ref "JP15") (pin "9") (pinfunction "9_9") (pintype "passive"))
      (node (ref "U1") (pin "54") (pinfunction "FSMC_A8/PF14_54") (pintype "passive"))
    )
    (net (code "99") (name "/PF15") (class "Default")
      (node (ref "JP15") (pin "10") (pinfunction "10_10") (pintype "passive"))
      (node (ref "U1") (pin "55") (pinfunction "FSMC_A9/PF15_55") (pintype "passive"))
    )
    (net (code "100") (name "/PG0") (class "Default")
      (node (ref "JP15") (pin "11") (pinfunction "11_11") (pintype "passive"))
      (node (ref "U1") (pin "56") (pinfunction "FSMC_A10/PG0_56") (pintype "passive"))
    )
    (net (code "101") (name "/PG1_KEY3") (class "Default")
      (node (ref "JP6") (pin "4") (pinfunction "4_4") (pintype "passive"))
      (node (ref "U1") (pin "57") (pinfunction "FSMC_A11/PG1_57") (pintype "passive"))
    )
    (net (code "102") (name "/PG2") (class "Default")
      (node (ref "JP15") (pin "12") (pinfunction "12_12") (pintype "passive"))
      (node (ref "U1") (pin "87") (pinfunction "FSMC_A12/PG2_87") (pintype "passive"))
    )
    (net (code "103") (name "/PG12_FSMC_NE4") (class "Default")
      (node (ref "J1") (pin "32") (pinfunction "32_32") (pintype "passive"))
      (node (ref "U1") (pin "127") (pinfunction "USART6_RTS/FSMC_NE4/PG12_127") (pintype "passive"))
    )
    (net (code "104") (name "/RST") (class "Default")
      (node (ref "J1") (pin "28") (pinfunction "28_28") (pintype "passive"))
      (node (ref "R3") (pin "2") (pinfunction "2_2") (pintype "passive"))
      (node (ref "SW2") (pin "1") (pinfunction "1_1") (pintype "passive"))
      (node (ref "U1") (pin "25") (pinfunction "NRST_25") (pintype "passive"))
    )
    (net (code "105") (name "/SWCLK") (class "Default")
      (node (ref "JP12") (pin "2") (pinfunction "2_2") (pintype "passive"))
      (node (ref "U1") (pin "109") (pinfunction "PA14/SWCLK_109") (pintype "passive"))
    )
    (net (code "106") (name "/SWDIO") (class "Default")
      (node (ref "JP12") (pin "3") (pinfunction "3_3") (pintype "passive"))
      (node (ref "U1") (pin "105") (pinfunction "PA13/SWDIO_105") (pintype "passive"))
    )
    (net (code "107") (name "/T_CS") (class "Default")
      (node (ref "J1") (pin "2") (pinfunction "2_2") (pintype "passive"))
      (node (ref "R7") (pin "1") (pinfunction "1_1") (pintype "passive"))
    )
    (net (code "108") (name "/T_MISO") (class "Default")
      (node (ref "J1") (pin "5") (pinfunction "5_5") (pintype "passive"))
      (node (ref "R4") (pin "1") (pinfunction "1_1") (pintype "passive"))
    )
    (net (code "109") (name "/T_MOSI") (class "Default")
      (node (ref "J1") (pin "4") (pinfunction "4_4") (pintype "passive"))
      (node (ref "R5") (pin "1") (pinfunction "1_1") (pintype "passive"))
    )
    (net (code "110") (name "/T_PEN") (class "Default")
      (node (ref "J1") (pin "3") (pinfunction "3_3") (pintype "passive"))
      (node (ref "R6") (pin "1") (pinfunction "1_1") (pintype "passive"))
    )
    (net (code "111") (name "/T_SCLK") (class "Default")
      (node (ref "J1") (pin "1") (pinfunction "1_1") (pintype "passive"))
      (node (ref "R8") (pin "1") (pinfunction "1_1") (pintype "passive"))
    )
    (net (code "112") (name "/VBAT") (class "Default")
      (node (ref "D1") (pin "3") (pinfunction "K_3") (pintype "passive"))
      (node (ref "U1") (pin "6") (pinfunction "VBAT_6") (pintype "passive"))
    )
    (net (code "113") (name "/VBAT_PIN_IN") (class "Default")
      (node (ref "D1") (pin "2") (pinfunction "A_2") (pintype "passive"))
      (node (ref "JP9") (pin "1") (pinfunction "1_1") (pintype "passive"))
    )
    (net (code "114") (name "/VCAP1") (class "Default")
      (node (ref "C10") (pin "2") (pinfunction "2_2") (pintype "passive"))
      (node (ref "U1") (pin "71") (pinfunction "VCAP_1_71") (pintype "passive"))
    )
    (net (code "115") (name "/VCAP2") (class "Default")
      (node (ref "C11") (pin "2") (pinfunction "2_2") (pintype "passive"))
      (node (ref "U1") (pin "106") (pinfunction "VCAP_2_106") (pintype "passive"))
    )
    (net (code "116") (name "/VREF+") (class "Default")
      (node (ref "C8") (pin "2") (pinfunction "2_2") (pintype "passive"))
      (node (ref "C9") (pin "2") (pinfunction "2_2") (pintype "passive"))
      (node (ref "R9") (pin "1") (pinfunction "1_1") (pintype "passive"))
      (node (ref "U1") (pin "32") (pinfunction "VREF+_32") (pintype "passive"))
    )
    (net (code "117") (name "3V3") (class "Default")
      (node (ref "C12") (pin "2") (pinfunction "2_2") (pintype "passive"))
      (node (ref "C13") (pin "2") (pinfunction "2_2") (pintype "passive"))
      (node (ref "C4") (pin "2") (pinfunction "2_2") (pintype "passive"))
      (node (ref "D1") (pin "1") (pinfunction "A_1") (pintype "passive"))
      (node (ref "DE1") (pin "1") (pinfunction "1_1") (pintype "passive"))
      (node (ref "J1") (pin "10") (pinfunction "10_10") (pintype "passive"))
      (node (ref "J1") (pin "9") (pinfunction "9_9") (pintype "passive"))
      (node (ref "JP11") (pin "4") (pinfunction "4_4") (pintype "passive"))
      (node (ref "JP12") (pin "4") (pinfunction "4_4") (pintype "passive"))
      (node (ref "JP13") (pin "4") (pinfunction "4_4") (pintype "passive"))
      (node (ref "JP16") (pin "4") (pinfunction "4_4") (pintype "passive"))
      (node (ref "R10") (pin "1") (pinfunction "1_1") (pintype "passive"))
      (node (ref "R11") (pin "1") (pinfunction "1_1") (pintype "passive"))
      (node (ref "R2") (pin "2") (pinfunction "2_2") (pintype "passive"))
      (node (ref "R3") (pin "1") (pinfunction "1_1") (pintype "passive"))
      (node (ref "R9") (pin "2") (pinfunction "2_2") (pintype "passive"))
      (node (ref "U1") (pin "108") (pinfunction "VDD_108") (pintype "passive"))
      (node (ref "U1") (pin "121") (pinfunction "VDD_121") (pintype "passive"))
      (node (ref "U1") (pin "131") (pinfunction "VDD_131") (pintype "passive"))
      (node (ref "U1") (pin "144") (pinfunction "VDD_144") (pintype "passive"))
      (node (ref "U1") (pin "17") (pinfunction "VDD_17") (pintype "passive"))
      (node (ref "U1") (pin "30") (pinfunction "VDD_30") (pintype "passive"))
      (node (ref "U1") (pin "33") (pinfunction "VDDA_33") (pintype "passive"))
      (node (ref "U1") (pin "39") (pinfunction "VDD_39") (pintype "passive"))
      (node (ref "U1") (pin "52") (pinfunction "VDD_52") (pintype "passive"))
      (node (ref "U1") (pin "62") (pinfunction "VDD_62") (pintype "passive"))
      (node (ref "U1") (pin "72") (pinfunction "VDD_72") (pintype "passive"))
      (node (ref "U1") (pin "84") (pinfunction "VDD_84") (pintype "passive"))
      (node (ref "U1") (pin "95") (pinfunction "VDD_95") (pintype "passive"))
    )
    (net (code "118") (name "GND") (class "Default")
      (node (ref "C1") (pin "2") (pinfunction "2_2") (pintype "passive"))
      (node (ref "C10") (pin "1") (pinfunction "1_1") (pintype "passive"))
      (node (ref "C11") (pin "1") (pinfunction "1_1") (pintype "passive"))
      (node (ref "C12") (pin "1") (pinfunction "1_1") (pintype "passive"))
      (node (ref "C13") (pin "1") (pinfunction "1_1") (pintype "passive"))
      (node (ref "C2") (pin "2") (pinfunction "2_2") (pintype "passive"))
      (node (ref "C3") (pin "2") (pinfunction "2_2") (pintype "passive"))
      (node (ref "C4") (pin "1") (pinfunction "1_1") (pintype "passive"))
      (node (ref "C5") (pin "1") (pinfunction "1_1") (pintype "passive"))
      (node (ref "C6") (pin "2") (pinfunction "2_2") (pintype "passive"))
      (node (ref "C8") (pin "1") (pinfunction "1_1") (pintype "passive"))
      (node (ref "C9") (pin "1") (pinfunction "1_1") (pintype "passive"))
      (node (ref "DE1") (pin "2") (pinfunction "2_2") (pintype "passive"))
      (node (ref "DE2") (pin "2") (pinfunction "2_2") (pintype "passive"))
      (node (ref "J1") (pin "7") (pinfunction "7_7") (pintype "passive"))
      (node (ref "J1") (pin "8") (pinfunction "8_8") (pintype "passive"))
      (node (ref "JP1") (pin "2") (pinfunction "2_2") (pintype "passive"))
      (node (ref "JP1") (pin "4") (pinfunction "4_4") (pintype "passive"))
      (node (ref "JP1") (pin "6") (pinfunction "6_6") (pintype "passive"))
      (node (ref "JP1") (pin "8") (pinfunction "8_8") (pintype "passive"))
      (node (ref "JP11") (pin "1") (pinfunction "1_1") (pintype "passive"))
      (node (ref "JP12") (pin "1") (pinfunction "1_1") (pintype "passive"))
      (node (ref "JP13") (pin "1") (pinfunction "1_1") (pintype "passive"))
      (node (ref "JP16") (pin "1") (pinfunction "1_1") (pintype "passive"))
      (node (ref "JP2") (pin "2") (pinfunction "2_2") (pintype "passive"))
      (node (ref "JP2") (pin "4") (pinfunction "4_4") (pintype "passive"))
      (node (ref "JP2") (pin "6") (pinfunction "6_6") (pintype "passive"))
      (node (ref "JP2") (pin "8") (pinfunction "8_8") (pintype "passive"))
      (node (ref "JP4") (pin "3") (pinfunction "3_3") (pintype "passive"))
      (node (ref "JP4") (pin "7") (pinfunction "7_7") (pintype "passive"))
      (node (ref "JP9") (pin "4") (pinfunction "4_4") (pintype "passive"))
      (node (ref "LED1") (pin "2") (pinfunction "K_2") (pintype "passive"))
      (node (ref "LED2") (pin "2") (pinfunction "K_2") (pintype "passive"))
      (node (ref "SW1") (pin "1") (pinfunction "1_1") (pintype "passive"))
      (node (ref "SW1") (pin "2") (pinfunction "2_2") (pintype "passive"))
      (node (ref "SW2") (pin "2") (pinfunction "2_2") (pintype "passive"))
      (node (ref "U1") (pin "107") (pinfunction "VSS_107") (pintype "passive"))
      (node (ref "U1") (pin "120") (pinfunction "VSS_120") (pintype "passive"))
      (node (ref "U1") (pin "130") (pinfunction "VSS_130") (pintype "passive"))
      (node (ref "U1") (pin "16") (pinfunction "VSS_16") (pintype "passive"))
      (node (ref "U1") (pin "31") (pinfunction "VSSA_31") (pintype "passive"))
      (node (ref "U1") (pin "38") (pinfunction "VSS_38") (pintype "passive"))
      (node (ref "U1") (pin "51") (pinfunction "VSS_51") (pintype "passive"))
      (node (ref "U1") (pin "61") (pinfunction "VSS_61") (pintype "passive"))
      (node (ref "U1") (pin "83") (pinfunction "VSS_83") (pintype "passive"))
      (node (ref "U1") (pin "94") (pinfunction "VSS_94") (pintype "passive"))
    )
    (net (code "119") (name "Net-(C7-Pad1)") (class "Default")
      (node (ref "C7") (pin "1") (pinfunction "1_1") (pintype "passive"))
      (node (ref "SW2") (pin "4") (pinfunction "4_4") (pintype "passive"))
    )
    (net (code "120") (name "Net-(C7-Pad2)") (class "Default")
      (node (ref "C7") (pin "2") (pinfunction "2_2") (pintype "passive"))
      (node (ref "SW2") (pin "3") (pinfunction "3_3") (pintype "passive"))
    )
    (net (code "121") (name "Net-(LED1-A)") (class "Default")
      (node (ref "LED1") (pin "1") (pinfunction "A_1") (pintype "passive"))
      (node (ref "R12") (pin "2") (pinfunction "2_2") (pintype "passive"))
    )
    (net (code "122") (name "Net-(LED2-A)") (class "Default")
      (node (ref "LED2") (pin "1") (pinfunction "A_1") (pintype "passive"))
      (node (ref "R13") (pin "2") (pinfunction "2_2") (pintype "passive"))
    )
    (net (code "123") (name "unconnected-(U1-FSMC_A13{slash}PG3-Pad88)") (class "Default")
      (node (ref "U1") (pin "88") (pinfunction "FSMC_A13/PG3_88") (pintype "passive+no_connect"))
    )
    (net (code "124") (name "unconnected-(U1-FSMC_A14{slash}PG4-Pad89)") (class "Default")
      (node (ref "U1") (pin "89") (pinfunction "FSMC_A14/PG4_89") (pintype "passive+no_connect"))
    )
    (net (code "125") (name "unconnected-(U1-FSMC_A15{slash}PG5-Pad90)") (class "Default")
      (node (ref "U1") (pin "90") (pinfunction "FSMC_A15/PG5_90") (pintype "passive+no_connect"))
    )
    (net (code "126") (name "unconnected-(U1-FSMC_INT2{slash}PG6-Pad91)") (class "Default")
      (node (ref "U1") (pin "91") (pinfunction "FSMC_INT2/PG6_91") (pintype "passive+no_connect"))
    )
    (net (code "127") (name "unconnected-(U1-FSMC_NCE4_1{slash}FSMC_NE3{slash}PG10-Pad125)") (class "Default")
      (node (ref "U1") (pin "125") (pinfunction "FSMC_NCE4_1/FSMC_NE3/PG10_125") (pintype "passive+no_connect"))
    )
    (net (code "128") (name "unconnected-(U1-FSMC_NCE4_2{slash}PG11-Pad126)") (class "Default")
      (node (ref "U1") (pin "126") (pinfunction "FSMC_NCE4_2/PG11_126") (pintype "passive+no_connect"))
    )
    (net (code "129") (name "unconnected-(U1-USART6_CK{slash}FSMC_INT3{slash}PG7-Pad92)") (class "Default")
      (node (ref "U1") (pin "92") (pinfunction "USART6_CK/FSMC_INT3/PG7_92") (pintype "passive+no_connect"))
    )
    (net (code "130") (name "unconnected-(U1-USART6_CTS{slash}FSMC_A24{slash}PG13-Pad128)") (class "Default")
      (node (ref "U1") (pin "128") (pinfunction "USART6_CTS/FSMC_A24/PG13_128") (pintype "passive+no_connect"))
    )
    (net (code "131") (name "unconnected-(U1-USART6_CTS{slash}PG15-Pad132)") (class "Default")
      (node (ref "U1") (pin "132") (pinfunction "USART6_CTS/PG15_132") (pintype "passive+no_connect"))
    )
    (net (code "132") (name "unconnected-(U1-USART6_RTS{slash}PG8-Pad93)") (class "Default")
      (node (ref "U1") (pin "93") (pinfunction "USART6_RTS/PG8_93") (pintype "passive+no_connect"))
    )
    (net (code "133") (name "unconnected-(U1-USART6_RX{slash}FSMC_NE2{slash}FSMC_NCE3{slash}PG9-Pad124)") (class "Default")
      (node (ref "U1") (pin "124") (pinfunction "USART6_RX/FSMC_NE2/FSMC_NCE3/PG9_124") (pintype "passive+no_connect"))
    )
    (net (code "134") (name "unconnected-(U1-USART6_TX{slash}FSMC_A25{slash}PG14-Pad129)") (class "Default")
      (node (ref "U1") (pin "129") (pinfunction "USART6_TX/FSMC_A25/PG14_129") (pintype "passive+no_connect"))
    )
    (net (code "135") (name "unconnected-(X1-Pad2)") (class "Default")
      (node (ref "X1") (pin "2") (pinfunction "2_2") (pintype "passive+no_connect"))
    )
    (net (code "136") (name "unconnected-(X1-Pad4)") (class "Default")
      (node (ref "X1") (pin "4") (pinfunction "4_4") (pintype "passive+no_connect"))
    )
  )
)
